# LNA_and_antenna.net
KiCad netlist of a schematic drawn in Altium Designer
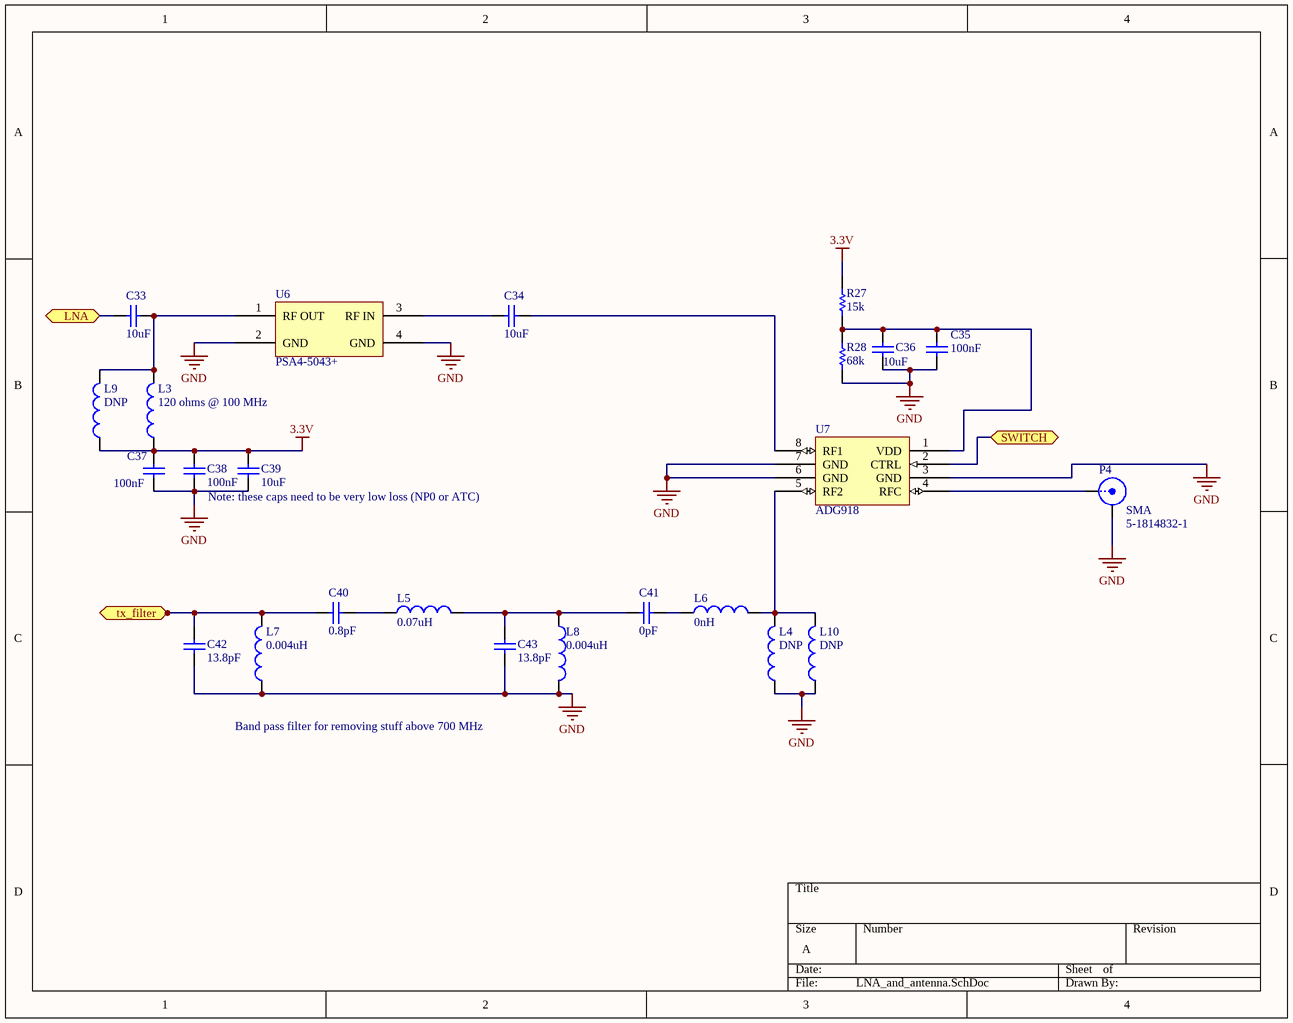
[diagram p0: LNA_and_antenna.SchDoc]

(export (version "E")
  (design (tool "Eeschema 10.0.6"))
  (components
    (comp (ref "C33")
      (value "10uF")
      (footprint "0402")
      (description "Capacitor (Semiconductor SIM Model)")
      (fields (field (name "Comment") "Cap Semi") (field (name "PUBLISHER") "Altium Limited"))
      (libsource (lib "Miscellaneous Devices") (part "Cap Semi"))
    )
    (comp (ref "C34")
      (value "10uF")
      (footprint "0402")
      (description "Capacitor (Semiconductor SIM Model)")
      (fields (field (name "Comment") "Cap Semi") (field (name "PUBLISHER") "Altium Limited"))
      (libsource (lib "Miscellaneous Devices") (part "Cap Semi"))
    )
    (comp (ref "C35")
      (value "100nF")
      (footprint "0402")
      (description "Capacitor (Semiconductor SIM Model)")
      (fields (field (name "Comment") "Cap Semi") (field (name "PUBLISHER") "Altium Limited"))
      (libsource (lib "Miscellaneous Devices") (part "Cap Semi"))
    )
    (comp (ref "C36")
      (value "10uF")
      (footprint "0402")
      (description "Capacitor (Semiconductor SIM Model)")
      (fields (field (name "Comment") "Cap Semi") (field (name "PUBLISHER") "Altium Limited"))
      (libsource (lib "Miscellaneous Devices") (part "Cap Semi"))
    )
    (comp (ref "C37")
      (value "100nF")
      (footprint "0402")
      (description "Capacitor (Semiconductor SIM Model)")
      (fields (field (name "Comment") "Cap Semi") (field (name "PUBLISHER") "Altium Limited"))
      (libsource (lib "Miscellaneous Devices") (part "Cap Semi"))
    )
    (comp (ref "C38")
      (value "100nF")
      (footprint "0402")
      (description "Capacitor (Semiconductor SIM Model)")
      (fields (field (name "Comment") "Cap Semi") (field (name "PUBLISHER") "Altium Limited"))
      (libsource (lib "Miscellaneous Devices") (part "Cap Semi"))
    )
    (comp (ref "C39")
      (value "10uF")
      (footprint "0402")
      (description "Capacitor (Semiconductor SIM Model)")
      (fields (field (name "Comment") "Cap Semi") (field (name "PUBLISHER") "Altium Limited"))
      (libsource (lib "Miscellaneous Devices") (part "Cap Semi"))
    )
    (comp (ref "C40")
      (value "0.8pF")
      (footprint "0402")
      (description "Capacitor (Semiconductor SIM Model)")
      (fields (field (name "Comment") "Cap Semi") (field (name "PUBLISHER") "Altium Limited"))
      (libsource (lib "Miscellaneous Devices") (part "Cap Semi"))
    )
    (comp (ref "C41")
      (value "0pF")
      (footprint "0402")
      (description "Capacitor (Semiconductor SIM Model)")
      (fields (field (name "Comment") "Cap Semi") (field (name "PUBLISHER") "Altium Limited"))
      (libsource (lib "Miscellaneous Devices") (part "Cap Semi"))
    )
    (comp (ref "C42")
      (value "13.8pF")
      (footprint "0402")
      (description "Capacitor (Semiconductor SIM Model)")
      (fields (field (name "Comment") "Cap Semi") (field (name "PUBLISHER") "Altium Limited"))
      (libsource (lib "Miscellaneous Devices") (part "Cap Semi"))
    )
    (comp (ref "C43")
      (value "13.8pF")
      (footprint "0402")
      (description "Capacitor (Semiconductor SIM Model)")
      (fields (field (name "Comment") "Cap Semi") (field (name "PUBLISHER") "Altium Limited"))
      (libsource (lib "Miscellaneous Devices") (part "Cap Semi"))
    )
    (comp (ref "L3")
      (value "120 ohms @ 100 MHz")
      (footprint "0402")
      (description "Inductor")
      (fields (field (name "PUBLISHER") "Altium Limited"))
      (libsource (lib "Miscellaneous Devices") (part "Inductor"))
    )
    (comp (ref "L4")
      (value "DNP")
      (footprint "0402")
      (description "Inductor")
      (fields (field (name "PUBLISHER") "Altium Limited"))
      (libsource (lib "Miscellaneous Devices") (part "Inductor"))
    )
    (comp (ref "L5")
      (value "0.07uH")
      (footprint "0402")
      (description "Inductor")
      (fields (field (name "PUBLISHER") "Altium Limited"))
      (libsource (lib "Miscellaneous Devices") (part "Inductor"))
    )
    (comp (ref "L6")
      (value "0nH")
      (footprint "0402")
      (description "Inductor")
      (fields (field (name "PUBLISHER") "Altium Limited"))
      (libsource (lib "Miscellaneous Devices") (part "Inductor"))
    )
    (comp (ref "L7")
      (value "0.004uH")
      (footprint "0402")
      (description "Inductor")
      (fields (field (name "PUBLISHER") "Altium Limited"))
      (libsource (lib "Miscellaneous Devices") (part "Inductor"))
    )
    (comp (ref "L8")
      (value "0.004uH")
      (footprint "0402")
      (description "Inductor")
      (fields (field (name "PUBLISHER") "Altium Limited"))
      (libsource (lib "Miscellaneous Devices") (part "Inductor"))
    )
    (comp (ref "L9")
      (value "DNP")
      (footprint "0402")
      (description "Inductor")
      (fields (field (name "PUBLISHER") "Altium Limited"))
      (libsource (lib "Miscellaneous Devices") (part "Inductor"))
    )
    (comp (ref "L10")
      (value "DNP")
      (footprint "0402")
      (description "Inductor")
      (fields (field (name "PUBLISHER") "Altium Limited"))
      (libsource (lib "Miscellaneous Devices") (part "Inductor"))
    )
    (comp (ref "P4")
      (value "SMA")
      (footprint "SMB_V-RJ45")
      (description "SMB Straight Connector")
      (fields (field (name "PUBLISHER") "Altium Limited"))
      (libsource (lib "Miscellaneous Connectors") (part "SMB"))
    )
    (comp (ref "R27")
      (value "15k")
      (footprint "0402")
      (description "Semiconductor Resistor")
      (fields (field (name "Comment") "Res Semi") (field (name "PUBLISHER") "Altium Limited"))
      (libsource (lib "Miscellaneous Devices") (part "Res Semi"))
    )
    (comp (ref "R28")
      (value "68k")
      (footprint "0402")
      (description "Semiconductor Resistor")
      (fields (field (name "Comment") "Res Semi") (field (name "PUBLISHER") "Altium Limited"))
      (libsource (lib "Miscellaneous Devices") (part "Res Semi"))
    )
    (comp (ref "U6")
      (value "PSA4-5043+")
      (description "LNA")
      (libsource (lib "shield_components") (part "PSA4-5043+"))
    )
    (comp (ref "U7")
      (value "ADG918")
      (footprint "ADG918")
      (description "RF Switch")
      (fields
        (field (name "MANUFACTURER") "Analog Devices Inc")
        (field (name "MANUFACTURER PART NUMBER") "ADG918BRMZ")
      )
      (libsource (lib "Parts") (part "ADG918"))
    )
  )
  (nets
    (net (code "1") (name "/LNA") (class "Default")
      (node (ref "C33") (pin "2") (pinfunction "2_2") (pintype "passive"))
    )
    (net (code "2") (name "/SWITCH") (class "Default")
      (node (ref "U7") (pin "2") (pinfunction "CTRL_2") (pintype "input"))
    )
    (net (code "3") (name "/tx_filter") (class "Default")
      (node (ref "C40") (pin "2") (pinfunction "2_2") (pintype "passive"))
      (node (ref "C42") (pin "1") (pinfunction "1_1") (pintype "passive"))
      (node (ref "L7") (pin "2") (pinfunction "2_2") (pintype "passive"))
    )
    (net (code "4") (name "3.3V") (class "Default")
      (node (ref "C37") (pin "1") (pinfunction "1_1") (pintype "passive"))
      (node (ref "C38") (pin "1") (pinfunction "1_1") (pintype "passive"))
      (node (ref "C39") (pin "1") (pinfunction "1_1") (pintype "passive"))
      (node (ref "L3") (pin "1") (pinfunction "1_1") (pintype "passive"))
      (node (ref "L9") (pin "1") (pinfunction "1_1") (pintype "passive"))
      (node (ref "R27") (pin "1") (pinfunction "1_1") (pintype "passive"))
    )
    (net (code "5") (name "GND") (class "Default")
      (node (ref "C35") (pin "1") (pinfunction "1_1") (pintype "passive"))
      (node (ref "C36") (pin "1") (pinfunction "1_1") (pintype "passive"))
      (node (ref "C37") (pin "2") (pinfunction "2_2") (pintype "passive"))
      (node (ref "C38") (pin "2") (pinfunction "2_2") (pintype "passive"))
      (node (ref "C39") (pin "2") (pinfunction "2_2") (pintype "passive"))
      (node (ref "C42") (pin "2") (pinfunction "2_2") (pintype "passive"))
      (node (ref "C43") (pin "2") (pinfunction "2_2") (pintype "passive"))
      (node (ref "L10") (pin "1") (pinfunction "1_1") (pintype "passive"))
      (node (ref "L4") (pin "1") (pinfunction "1_1") (pintype "passive"))
      (node (ref "L7") (pin "1") (pinfunction "1_1") (pintype "passive"))
      (node (ref "L8") (pin "2") (pinfunction "2_2") (pintype "passive"))
      (node (ref "P4") (pin "2") (pinfunction "Y_2") (pintype "passive"))
      (node (ref "R28") (pin "2") (pinfunction "2_2") (pintype "passive"))
      (node (ref "U6") (pin "2") (pinfunction "GND_2") (pintype "passive"))
      (node (ref "U6") (pin "4") (pinfunction "GND_4") (pintype "passive"))
      (node (ref "U7") (pin "3") (pinfunction "GND_3") (pintype "power_in"))
      (node (ref "U7") (pin "6") (pinfunction "GND_6") (pintype "power_in"))
      (node (ref "U7") (pin "7") (pinfunction "GND_7") (pintype "power_in"))
    )
    (net (code "6") (name "Net-(C40-Pad1)") (class "Default")
      (node (ref "C40") (pin "1") (pinfunction "1_1") (pintype "passive"))
      (node (ref "L5") (pin "1") (pinfunction "1_1") (pintype "passive"))
    )
    (net (code "7") (name "Net-(C41-Pad1)") (class "Default")
      (node (ref "C41") (pin "1") (pinfunction "1_1") (pintype "passive"))
      (node (ref "L6") (pin "1") (pinfunction "1_1") (pintype "passive"))
    )
    (net (code "8") (name "Net-(C41-Pad2)") (class "Default")
      (node (ref "C41") (pin "2") (pinfunction "2_2") (pintype "passive"))
      (node (ref "C43") (pin "1") (pinfunction "1_1") (pintype "passive"))
      (node (ref "L5") (pin "2") (pinfunction "2_2") (pintype "passive"))
      (node (ref "L8") (pin "1") (pinfunction "1_1") (pintype "passive"))
    )
    (net (code "9") (name "Net-(P4-X)") (class "Default")
      (node (ref "P4") (pin "1") (pinfunction "X_1") (pintype "passive"))
      (node (ref "U7") (pin "4") (pinfunction "RFC_4") (pintype "bidirectional"))
    )
    (net (code "10") (name "Net-(U6-RF_IN)") (class "Default")
      (node (ref "C34") (pin "2") (pinfunction "2_2") (pintype "passive"))
      (node (ref "U6") (pin "3") (pinfunction "RF_IN_3") (pintype "passive"))
    )
    (net (code "11") (name "Net-(U6-RF_OUT)") (class "Default")
      (node (ref "C33") (pin "1") (pinfunction "1_1") (pintype "passive"))
      (node (ref "L3") (pin "2") (pinfunction "2_2") (pintype "passive"))
      (node (ref "L9") (pin "2") (pinfunction "2_2") (pintype "passive"))
      (node (ref "U6") (pin "1") (pinfunction "RF_OUT_1") (pintype "passive"))
    )
    (net (code "12") (name "Net-(U7-RF1)") (class "Default")
      (node (ref "C34") (pin "1") (pinfunction "1_1") (pintype "passive"))
      (node (ref "U7") (pin "8") (pinfunction "RF1_8") (pintype "bidirectional"))
    )
    (net (code "13") (name "Net-(U7-RF2)") (class "Default")
      (node (ref "L10") (pin "2") (pinfunction "2_2") (pintype "passive"))
      (node (ref "L4") (pin "2") (pinfunction "2_2") (pintype "passive"))
      (node (ref "L6") (pin "2") (pinfunction "2_2") (pintype "passive"))
      (node (ref "U7") (pin "5") (pinfunction "RF2_5") (pintype "bidirectional"))
    )
    (net (code "14") (name "Net-(U7-VDD)") (class "Default")
      (node (ref "C35") (pin "2") (pinfunction "2_2") (pintype "passive"))
      (node (ref "C36") (pin "2") (pinfunction "2_2") (pintype "passive"))
      (node (ref "R27") (pin "2") (pinfunction "2_2") (pintype "passive"))
      (node (ref "R28") (pin "1") (pinfunction "1_1") (pintype "passive"))
      (node (ref "U7") (pin "1") (pinfunction "VDD_1") (pintype "power_in"))
    )
  )
)
